# attenuator.net
KiCad netlist of a schematic drawn in Altium Designer
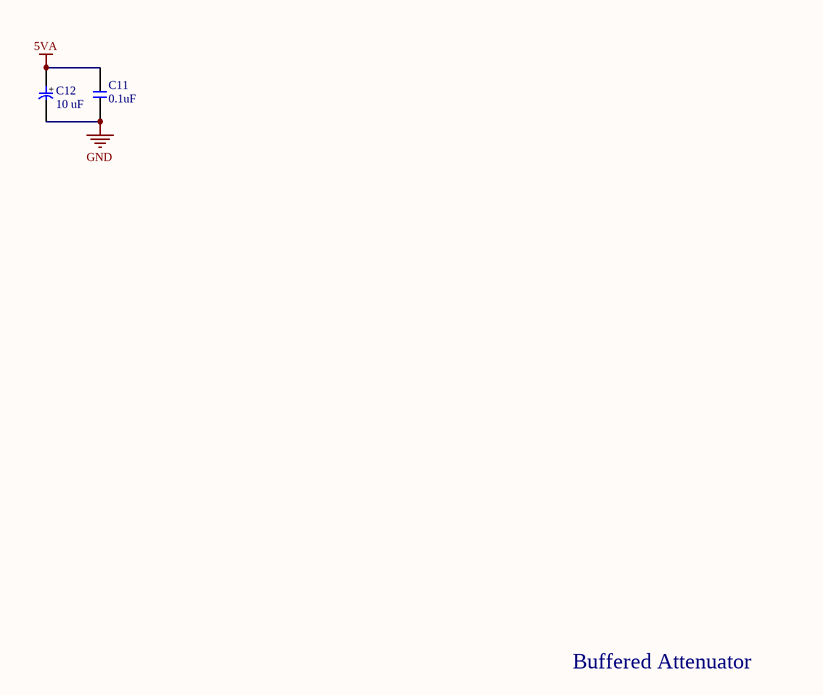
[diagram p0: attenuator.SchDoc]

(export (version "E")
  (design (tool "Eeschema 10.0.6"))
  (components
    (comp (ref "C11") (value "0.1uF") (footprint "0603") (libsource (lib "tester_board") (part "C0.1uF")))
    (comp (ref "C12")
      (value "10 uF")
      (footprint "KEMET 1411")
      (libsource (lib "tester_board") (part "C10uF Electro."))
    )
  )
  (nets
    (net (code "1") (name "5VA") (class "Default")
      (node (ref "C11") (pin "2") (pinfunction "2_2") (pintype "passive"))
      (node (ref "C12") (pin "1") (pinfunction "+_1") (pintype "passive"))
    )
    (net (code "2") (name "GND") (class "Default")
      (node (ref "C11") (pin "1") (pinfunction "5_1") (pintype "passive"))
      (node (ref "C12") (pin "2") (pinfunction "-_2") (pintype "passive"))
    )
  )
)
